# SCH_Link-Card_2024-12-06.net
KiCad netlist of a schematic drawn in EasyEDA
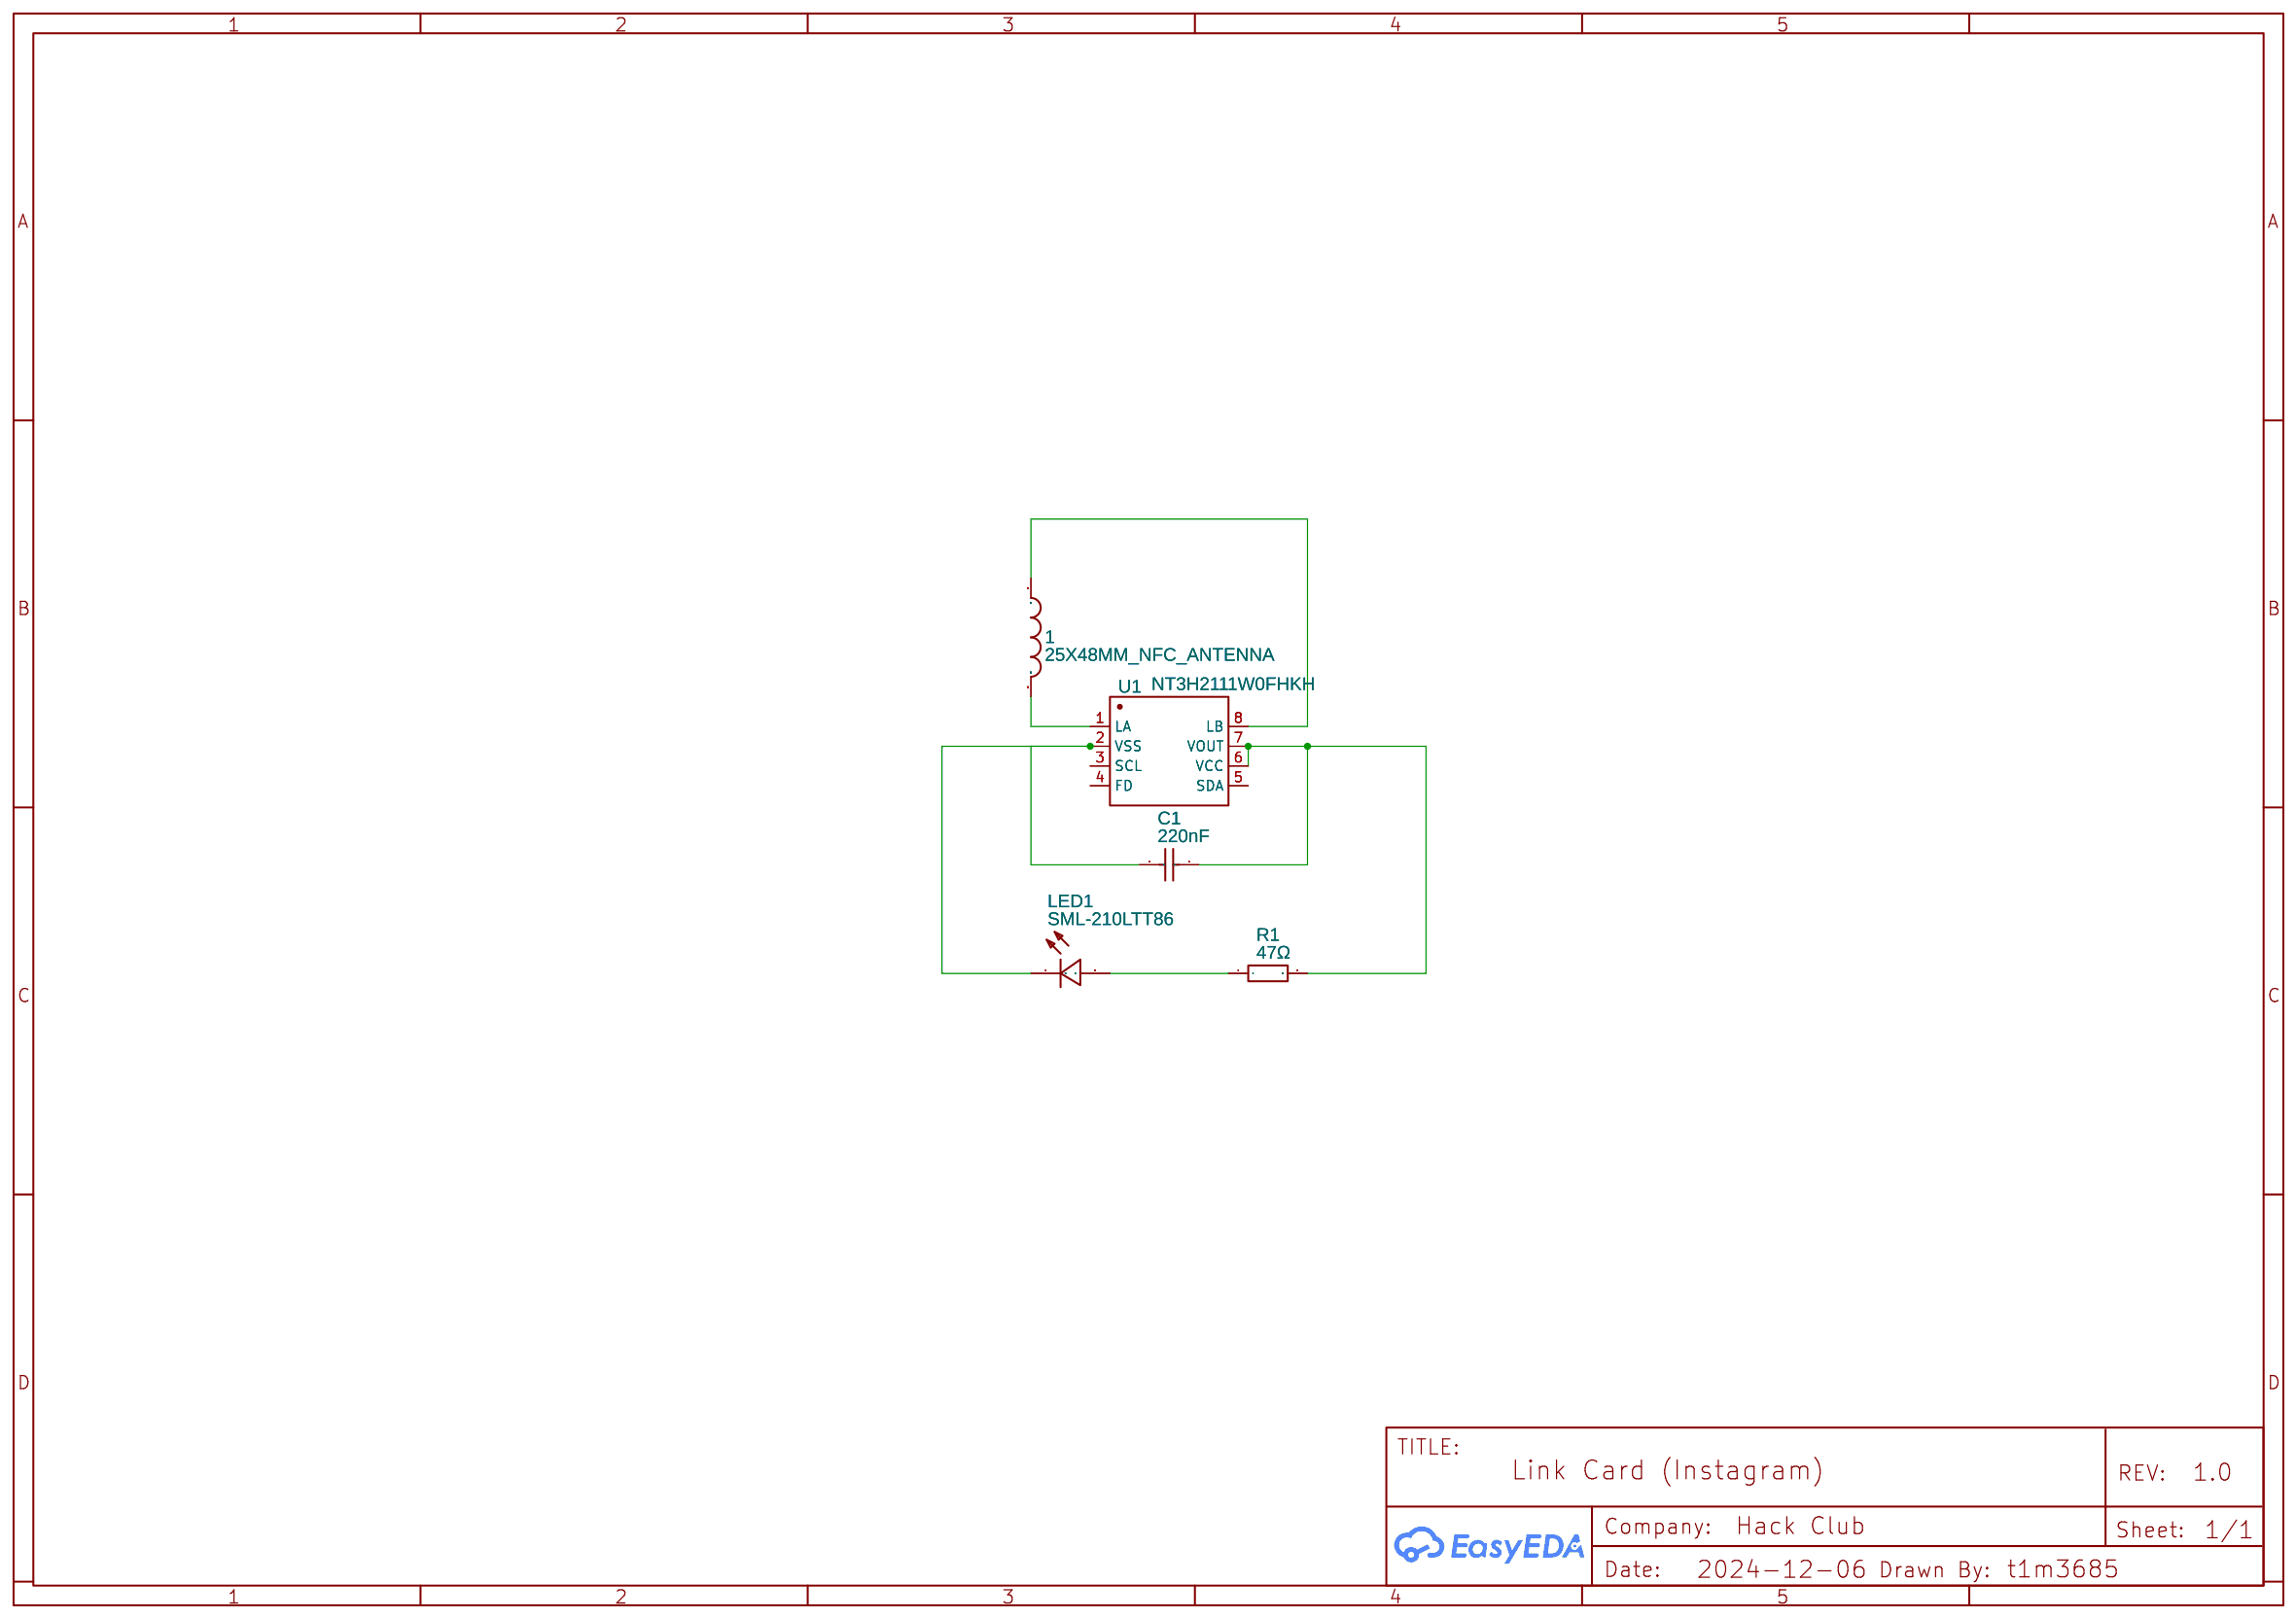
[diagram p0: schematic sheet]

(export (version "E")
  (design (tool "Eeschema 10.0.6"))
  (components
    (comp (ref "1") (value "25X48MM_NFC_ANTENNA") (libsource (lib "") (part "25X48MM_NFC_ANTENNA")))
    (comp (ref "C1")
      (value "220nF")
      (fields
        (field (name "Manufacturer Part") "CL10B224KA8NNNC")
        (field (name "Manufacturer") "SAMSUNG(三星)")
      )
      (libsource (lib "") (part "CL10B224KA8NNNC"))
    )
    (comp (ref "LED1")
      (value "SML-210LTT86")
      (fields (field (name "Manufacturer") "ROHM(罗姆)"))
      (libsource (lib "") (part "SML-210LTT86"))
    )
    (comp (ref "R1")
      (value "47Ω")
      (fields
        (field (name "Manufacturer Part") "0603WAF470JT5E")
        (field (name "Manufacturer") "UNI-ROYAL(厚声)")
      )
      (libsource (lib "") (part "0603WAF470JT5E"))
    )
    (comp (ref "U1")
      (value "NT3H2111W0FHKH")
      (fields (field (name "Manufacturer") "NXP(恩智浦)"))
      (libsource (lib "") (part "NT3H2111W0FHKH"))
    )
  )
  (nets
    (net (code "1") (name "Net-(LED1-A)") (class "Default")
      (node (ref "LED1") (pin "2") (pinfunction "A_2") (pintype "unspecified"))
      (node (ref "R1") (pin "1") (pinfunction "1_1") (pintype "input"))
    )
    (net (code "2") (name "Net-(LED1-C)") (class "Default")
      (node (ref "C1") (pin "1") (pinfunction "1_1") (pintype "input"))
      (node (ref "LED1") (pin "1") (pinfunction "C_1") (pintype "unspecified"))
      (node (ref "U1") (pin "2") (pinfunction "VSS_2") (pintype "unspecified"))
    )
    (net (code "3") (name "Net-(U1-LA)") (class "Default")
      (node (ref "1") (pin "P$2") (pinfunction "P$2_P$2") (pintype "bidirectional"))
      (node (ref "U1") (pin "1") (pinfunction "LA_1") (pintype "unspecified"))
    )
    (net (code "4") (name "Net-(U1-LB)") (class "Default")
      (node (ref "1") (pin "P$1") (pinfunction "P$1_P$1") (pintype "bidirectional"))
      (node (ref "U1") (pin "8") (pinfunction "LB_8") (pintype "unspecified"))
    )
    (net (code "5") (name "Net-(U1-VCC)") (class "Default")
      (node (ref "C1") (pin "2") (pinfunction "2_2") (pintype "input"))
      (node (ref "R1") (pin "2") (pinfunction "2_2") (pintype "input"))
      (node (ref "U1") (pin "6") (pinfunction "VCC_6") (pintype "unspecified"))
      (node (ref "U1") (pin "7") (pinfunction "VOUT_7") (pintype "unspecified"))
    )
    (net (code "6") (name "unconnected-(U1-FD-Pad4)") (class "Default")
      (node (ref "U1") (pin "4") (pinfunction "FD_4") (pintype "unspecified"))
    )
    (net (code "7") (name "unconnected-(U1-SCL-Pad3)") (class "Default")
      (node (ref "U1") (pin "3") (pinfunction "SCL_3") (pintype "unspecified"))
    )
    (net (code "8") (name "unconnected-(U1-SDA-Pad5)") (class "Default")
      (node (ref "U1") (pin "5") (pinfunction "SDA_5") (pintype "unspecified"))
    )
  )
)
